# STM_Power_Supply.net
KiCad netlist of a schematic drawn in Altium Designer
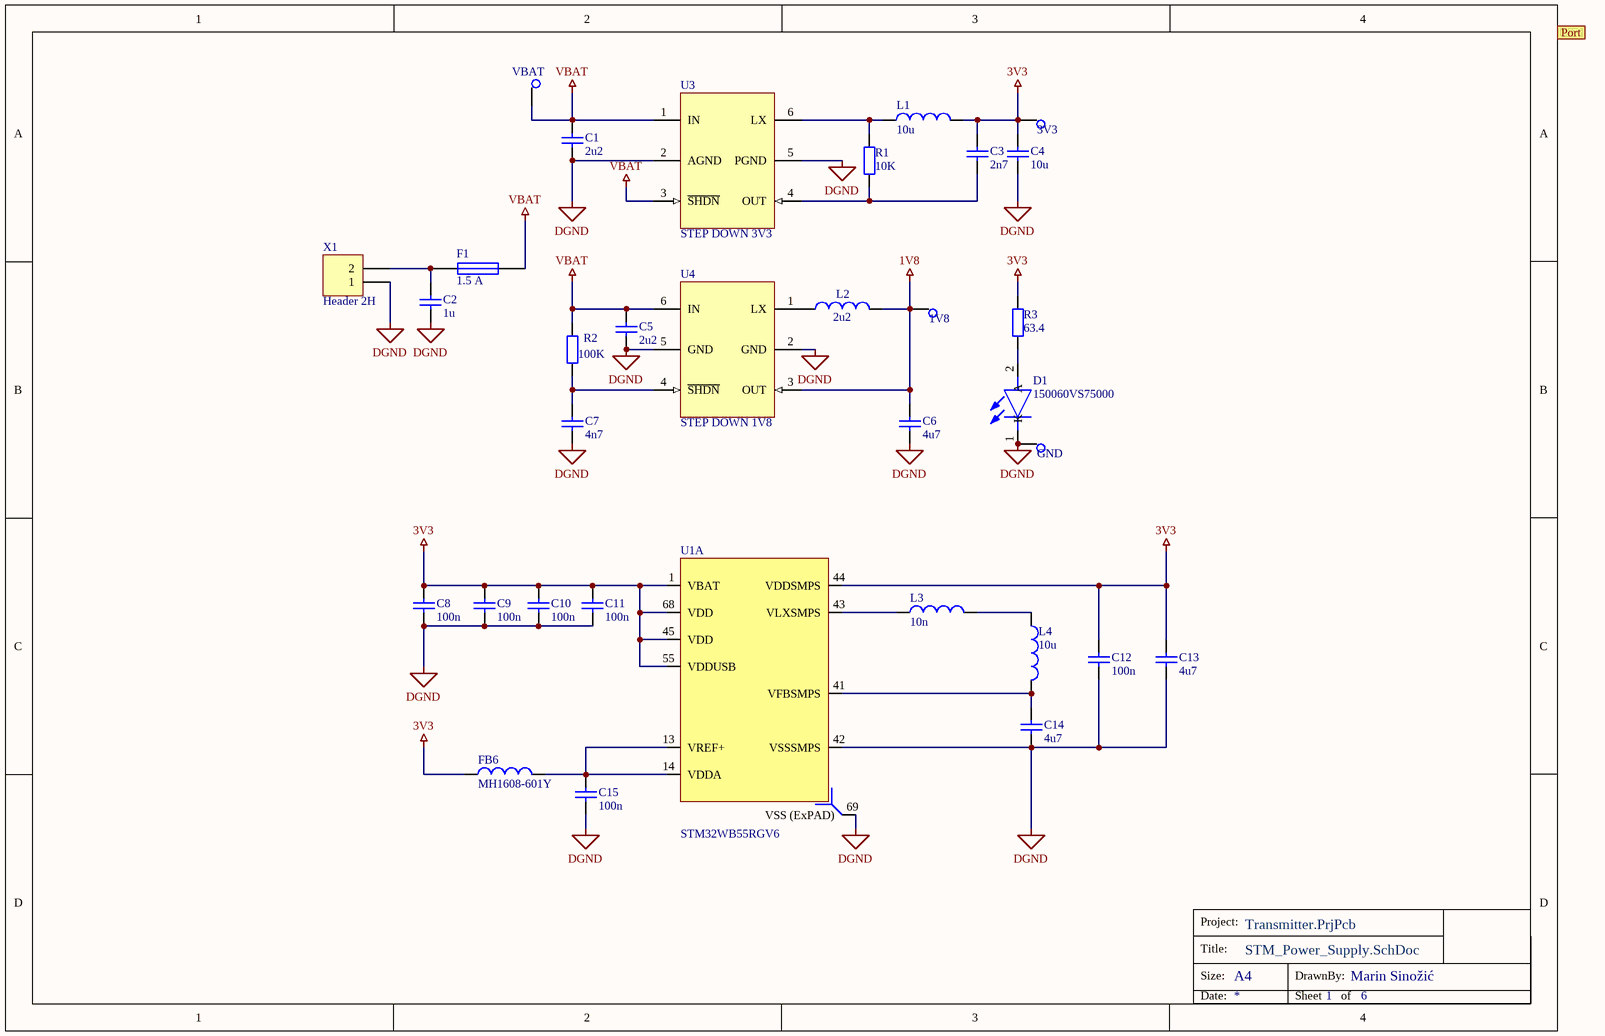
[diagram p0: STM_Power_Supply.SchDoc]

(export (version "E")
  (design (tool "Eeschema 10.0.6"))
  (components
    (comp (ref "1V8") (value "TestPoint") (footprint "TP") (libsource (lib "Transmitter") (part "TestPoint")))
    (comp (ref "3V3") (value "TestPoint") (footprint "TP") (libsource (lib "Transmitter") (part "TestPoint")))
    (comp (ref "C1")
      (value "2u2")
      (footprint "0603")
      (description "CAP CER 2.2UF 25V X5R 0603")
      (fields (field (name "MANUFACTURER PART NUMBER") "490-10731-1-ND"))
      (libsource (lib "Miscellaneous Devices") (part "Cap"))
    )
    (comp (ref "C2")
      (value "1u")
      (footprint "0805")
      (description "CAP CER 1UF 25V X5R 0805")
      (fields (field (name "MANUFACTURER PART NUMBER") "311-1868-1-ND"))
      (libsource (lib "Miscellaneous Devices") (part "Cap"))
    )
    (comp (ref "C3")
      (value "2n7")
      (footprint "0603")
      (description "CAP CER 2700PF 50V X7R 0603")
      (fields (field (name "MANUFACTURER PART NUMBER") "1276-2022-1-ND"))
      (libsource (lib "Miscellaneous Devices") (part "Cap"))
    )
    (comp (ref "C4")
      (value "10u")
      (footprint "0603")
      (description "CAP CER 10UF 25V X5R 0603")
      (fields (field (name "MANUFACTURER PART NUMBER") "490-GRM188R61E106KA73JCT-ND"))
      (libsource (lib "Miscellaneous Devices") (part "Cap"))
    )
    (comp (ref "C5")
      (value "2u2")
      (footprint "0603")
      (description "CAP CER 2.2UF 25V X5R 0603")
      (fields (field (name "MANUFACTURER PART NUMBER") "490-10731-1-ND"))
      (libsource (lib "Miscellaneous Devices") (part "Cap"))
    )
    (comp (ref "C6")
      (value "4u7")
      (footprint "0603")
      (description "CAP CER 4.7UF 16V X5R 0603")
      (fields (field (name "MANUFACTURER PART NUMBER") "587-2786-1-ND"))
      (libsource (lib "Miscellaneous Devices") (part "Cap"))
    )
    (comp (ref "C7")
      (value "4n7")
      (footprint "0603")
      (description "CAP CER 4700PF 50V X7R 0603")
      (fields (field (name "MANUFACTURER PART NUMBER") "1276-1098-1-ND"))
      (libsource (lib "Miscellaneous Devices") (part "Cap"))
    )
    (comp (ref "C8")
      (value "100n")
      (footprint "0603")
      (description "CAP CER 0.1UF 50V X7R 0603")
      (fields (field (name "MANUFACTURER PART NUMBER") "1276-CL10B104KB8WPNDCT-ND"))
      (libsource (lib "Miscellaneous Devices") (part "Cap"))
    )
    (comp (ref "C9")
      (value "100n")
      (footprint "0603")
      (description "CAP CER 0.1UF 50V X7R 0603")
      (fields (field (name "MANUFACTURER PART NUMBER") "1276-CL10B104KB8WPNDCT-ND"))
      (libsource (lib "Miscellaneous Devices") (part "Cap"))
    )
    (comp (ref "C10")
      (value "100n")
      (footprint "0603")
      (description "CAP CER 0.1UF 50V X7R 0603")
      (fields (field (name "MANUFACTURER PART NUMBER") "1276-CL10B104KB8WPNDCT-ND"))
      (libsource (lib "Miscellaneous Devices") (part "Cap"))
    )
    (comp (ref "C11")
      (value "100n")
      (footprint "0603")
      (description "CAP CER 0.1UF 50V X7R 0603")
      (fields (field (name "MANUFACTURER PART NUMBER") "1276-CL10B104KB8WPNDCT-ND"))
      (libsource (lib "Miscellaneous Devices") (part "Cap"))
    )
    (comp (ref "C12")
      (value "100n")
      (footprint "0603")
      (description "CAP CER 0.1UF 50V X7R 0603")
      (fields (field (name "MANUFACTURER PART NUMBER") "1276-CL10B104KB8WPNDCT-ND"))
      (libsource (lib "Miscellaneous Devices") (part "Cap"))
    )
    (comp (ref "C13")
      (value "4u7")
      (footprint "0603")
      (description "CAP CER 4.7UF 16V X5R 0603")
      (fields (field (name "MANUFACTURER PART NUMBER") "587-2786-1-ND"))
      (libsource (lib "Miscellaneous Devices") (part "Cap"))
    )
    (comp (ref "C14")
      (value "4u7")
      (footprint "0603")
      (description "CAP CER 4.7UF 16V X5R 0603")
      (fields (field (name "MANUFACTURER PART NUMBER") "587-2786-1-ND"))
      (libsource (lib "Miscellaneous Devices") (part "Cap"))
    )
    (comp (ref "C15")
      (value "100n")
      (footprint "0603")
      (description "CAP CER 0.1UF 50V X7R 0603")
      (fields (field (name "MANUFACTURER PART NUMBER") "1276-CL10B104KB8WPNDCT-ND"))
      (libsource (lib "Miscellaneous Devices") (part "Cap"))
    )
    (comp (ref "D1")
      (value "150060VS75000")
      (footprint "0603")
      (description "LED GREEN DIFFUSED 0603 SMD")
      (fields (field (name "MANUFACTURER PART NUMBER") "732-12017-1-ND"))
      (libsource (lib "150060VS75000 (1)") (part "150060VS75000"))
    )
    (comp (ref "F1")
      (value "1.5 A")
      (footprint "MF-USMF075-2")
      (description "PTC RESET FUSE 6V 750MA 1210")
      (fields (field (name "MANUFACTURER PART NUMBER") "MF-USMF075-2CT-ND"))
      (libsource (lib "Miscellaneous Devices") (part "Fuse 1"))
    )
    (comp (ref "FB6")
      (value "MH1608-601Y")
      (footprint "0603")
      (description "FERRITE BEAD 600 OHM 0603 1LN")
      (fields (field (name "MANUFACTURER PART NUMBER") "MH1608-601YCT-ND"))
      (libsource (lib "Tx_board") (part "MH1608-601Y"))
    )
    (comp (ref "GND") (value "TestPoint") (footprint "TP") (libsource (lib "Transmitter") (part "TestPoint")))
    (comp (ref "L1")
      (value "10u")
      (footprint "IND_10uH")
      (description "FIXED IND 10UH 550MA 210MOHM SMD")
      (fields (field (name "MANUFACTURER PART NUMBER") "308-2298-1-ND"))
      (libsource (lib "Tx_board") (part "L_0805_10uH"))
    )
    (comp (ref "L2")
      (value "2u2")
      (footprint "INDP2929X15N")
      (description "FIXED IND 2.2UH 1.22A 78MOHM SMD")
      (fields (field (name "MANUFACTURER PART NUMBER") "490-15950-1-ND"))
      (libsource (lib "") (part "L_0805_10uH_1"))
    )
    (comp (ref "L3")
      (value "10n")
      (footprint "0603")
      (description "FIXED IND 10NH 600MA 200MOHM SMD")
      (fields (field (name "MANUFACTURER PART NUMBER") "490-15244-1-ND"))
      (libsource (lib "Tx_board") (part "L_0805_10uH"))
    )
    (comp (ref "L4")
      (value "10u")
      (footprint "0805")
      (description "FIXED IND 10UH 100MA 780MOHM SMD")
      (fields (field (name "MANUFACTURER PART NUMBER") "490-4029-1-ND"))
      (libsource (lib "Tx_board") (part "L_0805_10uH"))
    )
    (comp (ref "R1")
      (value "10K")
      (footprint "0603")
      (description "RES SMD 10K OHM 0.5% 1/5W 0603")
      (fields (field (name "MANUFACTURER PART NUMBER") "P20397CT-ND"))
      (libsource (lib "Miscellaneous Devices") (part "Res2"))
    )
    (comp (ref "R2")
      (value "100K")
      (footprint "0603")
      (description "RES 100 KOHMS 0.5% 1/10W 0603")
      (fields (field (name "MANUFACTURER PART NUMBER") "P123902CT-ND"))
      (libsource (lib "") (part "Res2_1"))
    )
    (comp (ref "R3")
      (value "63.4")
      (footprint "0603")
      (description "RES SMD 63.4 OHM 0.1% 1/10W 0603")
      (fields (field (name "MANUFACTURER PART NUMBER") "YAG4584CT-ND"))
      (libsource (lib "Miscellaneous Devices") (part "Res2"))
    )
    (comp (ref "U1")
      (value "STM32WB55RGV6")
      (footprint "VFQFPN69")
      (description "MCU 32-Bit STM32WB55 ARM Cortex M4 RISC 1MB Flash 1.7V to 3.6V 68-Pin VFQFPN Tray")
      (fields (field (name "MANUFACTURER PART NUMBER") "497-18488-ND"))
      (libsource (lib "Transmitter") (part "STM32WB55RGV6"))
    )
    (comp (ref "U3")
      (value "STEP DOWN 3V3")
      (footprint "SOT95P280X145-6N")
      (description "IC REG BUCK 3.3V 400MA SOT23-6")
      (fields (field (name "MANUFACTURER PART NUMBER") "MAX1921EUT33+T-ND"))
      (libsource (lib "Transmitter") (part "MAX1921EUT33+T"))
    )
    (comp (ref "U4")
      (value "STEP DOWN 1V8")
      (footprint "SC70P20X21")
      (description "IC REG BUCK 1.8V 500MA SC70-6")
      (fields (field (name "MANUFACTURER PART NUMBER") "MAX8640YEXT18+TCT-ND"))
      (libsource (lib "Transmitter") (part "MAX8640YEXT18+T"))
    )
    (comp (ref "VBAT")
      (value "TestPoint")
      (footprint "TP")
      (libsource (lib "Transmitter") (part "TestPoint"))
    )
    (comp (ref "X1")
      (value "Header 2H")
      (footprint "HDR1X2")
      (description "Header, 2-Pin, Right Angle")
      (libsource (lib "Miscellaneous Connectors") (part "Header 2H"))
    )
  )
  (nets
    (net (code "2") (name "1V8") (class "Default")
      (node (ref "1V8") (pin "1") (pintype "passive"))
      (node (ref "C6") (pin "2") (pinfunction "2_2") (pintype "passive"))
      (node (ref "L2") (pin "1") (pinfunction "1_1") (pintype "passive"))
      (node (ref "U4") (pin "3") (pinfunction "OUT_3") (pintype "input"))
    )
    (net (code "3") (name "3V3") (class "Default")
      (node (ref "3V3") (pin "1") (pintype "passive"))
      (node (ref "C10") (pin "2") (pinfunction "2_2") (pintype "passive"))
      (node (ref "C11") (pin "2") (pinfunction "2_2") (pintype "passive"))
      (node (ref "C12") (pin "2") (pinfunction "2_2") (pintype "passive"))
      (node (ref "C13") (pin "1") (pinfunction "1_1") (pintype "passive"))
      (node (ref "C3") (pin "2") (pinfunction "2_2") (pintype "passive"))
      (node (ref "C4") (pin "2") (pinfunction "2_2") (pintype "passive"))
      (node (ref "C8") (pin "2") (pinfunction "2_2") (pintype "passive"))
      (node (ref "C9") (pin "2") (pinfunction "2_2") (pintype "passive"))
      (node (ref "FB6") (pin "1") (pinfunction "1_1") (pintype "passive"))
      (node (ref "L1") (pin "2") (pinfunction "2_2") (pintype "passive"))
      (node (ref "R3") (pin "2") (pinfunction "2_2") (pintype "passive"))
      (node (ref "U1") (pin "1") (pinfunction "VBAT_1") (pintype "power_in"))
      (node (ref "U1") (pin "44") (pinfunction "VDDSMPS_44") (pintype "power_in"))
      (node (ref "U1") (pin "45") (pinfunction "VDD_45") (pintype "power_in"))
      (node (ref "U1") (pin "55") (pinfunction "VDDUSB_55") (pintype "power_in"))
      (node (ref "U1") (pin "68") (pinfunction "VDD_68") (pintype "power_in"))
    )
    (net (code "4") (name "DGND") (class "Default")
      (node (ref "C1") (pin "1") (pinfunction "1_1") (pintype "passive"))
      (node (ref "C10") (pin "1") (pinfunction "1_1") (pintype "passive"))
      (node (ref "C11") (pin "1") (pinfunction "1_1") (pintype "passive"))
      (node (ref "C12") (pin "1") (pinfunction "1_1") (pintype "passive"))
      (node (ref "C13") (pin "2") (pinfunction "2_2") (pintype "passive"))
      (node (ref "C14") (pin "1") (pinfunction "1_1") (pintype "passive"))
      (node (ref "C15") (pin "1") (pinfunction "1_1") (pintype "passive"))
      (node (ref "C2") (pin "1") (pinfunction "1_1") (pintype "passive"))
      (node (ref "C4") (pin "1") (pinfunction "1_1") (pintype "passive"))
      (node (ref "C5") (pin "1") (pinfunction "1_1") (pintype "passive"))
      (node (ref "C6") (pin "1") (pinfunction "1_1") (pintype "passive"))
      (node (ref "C7") (pin "1") (pinfunction "1_1") (pintype "passive"))
      (node (ref "C8") (pin "1") (pinfunction "1_1") (pintype "passive"))
      (node (ref "C9") (pin "1") (pinfunction "1_1") (pintype "passive"))
      (node (ref "D1") (pin "1") (pinfunction "K_1") (pintype "bidirectional"))
      (node (ref "GND") (pin "1") (pintype "passive"))
      (node (ref "U1") (pin "42") (pinfunction "VSSSMPS_42") (pintype "power_in"))
      (node (ref "U1") (pin "69") (pinfunction "VSS_(ExPAD)_69") (pintype "power_in"))
      (node (ref "U3") (pin "2") (pinfunction "AGND_2") (pintype "power_in"))
      (node (ref "U3") (pin "5") (pinfunction "PGND_5") (pintype "power_in"))
      (node (ref "U4") (pin "2") (pinfunction "GND_2") (pintype "power_in"))
      (node (ref "U4") (pin "5") (pinfunction "GND_5") (pintype "power_in"))
      (node (ref "X1") (pin "1") (pinfunction "1_1") (pintype "passive"))
    )
    (net (code "5") (name "Net-(C2-Pad2)") (class "Default")
      (node (ref "C2") (pin "2") (pinfunction "2_2") (pintype "passive"))
      (node (ref "F1") (pin "1") (pinfunction "1_1") (pintype "passive"))
      (node (ref "X1") (pin "2") (pinfunction "2_2") (pintype "passive"))
    )
    (net (code "6") (name "Net-(D1-A)") (class "Default")
      (node (ref "D1") (pin "2") (pinfunction "A_2") (pintype "bidirectional"))
      (node (ref "R3") (pin "1") (pinfunction "1_1") (pintype "passive"))
    )
    (net (code "7") (name "Net-(L3-Pad2)") (class "Default")
      (node (ref "L3") (pin "2") (pinfunction "2_2") (pintype "passive"))
      (node (ref "L4") (pin "1") (pinfunction "1_1") (pintype "passive"))
    )
    (net (code "8") (name "Net-(U1A-VDDA)") (class "Default")
      (node (ref "C15") (pin "2") (pinfunction "2_2") (pintype "passive"))
      (node (ref "FB6") (pin "2") (pinfunction "2_2") (pintype "passive"))
      (node (ref "U1") (pin "13") (pinfunction "VREF+_13") (pintype "power_in"))
      (node (ref "U1") (pin "14") (pinfunction "VDDA_14") (pintype "power_in"))
    )
    (net (code "9") (name "Net-(U1A-VFBSMPS)") (class "Default")
      (node (ref "C14") (pin "2") (pinfunction "2_2") (pintype "passive"))
      (node (ref "L4") (pin "2") (pinfunction "2_2") (pintype "passive"))
      (node (ref "U1") (pin "41") (pinfunction "VFBSMPS_41") (pintype "power_in"))
    )
    (net (code "10") (name "Net-(U1A-VLXSMPS)") (class "Default")
      (node (ref "L3") (pin "1") (pinfunction "1_1") (pintype "passive"))
      (node (ref "U1") (pin "43") (pinfunction "VLXSMPS_43") (pintype "power_in"))
    )
    (net (code "11") (name "Net-(U3-LX)") (class "Default")
      (node (ref "L1") (pin "1") (pinfunction "1_1") (pintype "passive"))
      (node (ref "R1") (pin "2") (pinfunction "2_2") (pintype "passive"))
      (node (ref "U3") (pin "6") (pinfunction "LX_6") (pintype "passive"))
    )
    (net (code "12") (name "Net-(U3-OUT)") (class "Default")
      (node (ref "C3") (pin "1") (pinfunction "1_1") (pintype "passive"))
      (node (ref "R1") (pin "1") (pinfunction "1_1") (pintype "passive"))
      (node (ref "U3") (pin "4") (pinfunction "OUT_4") (pintype "input"))
    )
    (net (code "13") (name "Net-(U4-LX)") (class "Default")
      (node (ref "L2") (pin "2") (pinfunction "2_2") (pintype "passive"))
      (node (ref "U4") (pin "1") (pinfunction "LX_1") (pintype "passive"))
    )
    (net (code "14") (name "Net-(U4-~{SHDN})") (class "Default")
      (node (ref "C7") (pin "2") (pinfunction "2_2") (pintype "passive"))
      (node (ref "R2") (pin "1") (pinfunction "1_1") (pintype "passive"))
      (node (ref "U4") (pin "4") (pinfunction "~{SHDN}_4") (pintype "input"))
    )
    (net (code "15") (name "VBAT") (class "Default")
      (node (ref "C1") (pin "2") (pinfunction "2_2") (pintype "passive"))
      (node (ref "C5") (pin "2") (pinfunction "2_2") (pintype "passive"))
      (node (ref "F1") (pin "2") (pinfunction "2_2") (pintype "passive"))
      (node (ref "R2") (pin "2") (pinfunction "2_2") (pintype "passive"))
      (node (ref "U3") (pin "1") (pinfunction "IN_1") (pintype "power_in"))
      (node (ref "U3") (pin "3") (pinfunction "~{SHDN}_3") (pintype "input"))
      (node (ref "U4") (pin "6") (pinfunction "IN_6") (pintype "power_in"))
      (node (ref "VBAT") (pin "1") (pintype "passive"))
    )
  )
)
